# SCH_V1_3.net
KiCad netlist of a schematic drawn in Altium Designer
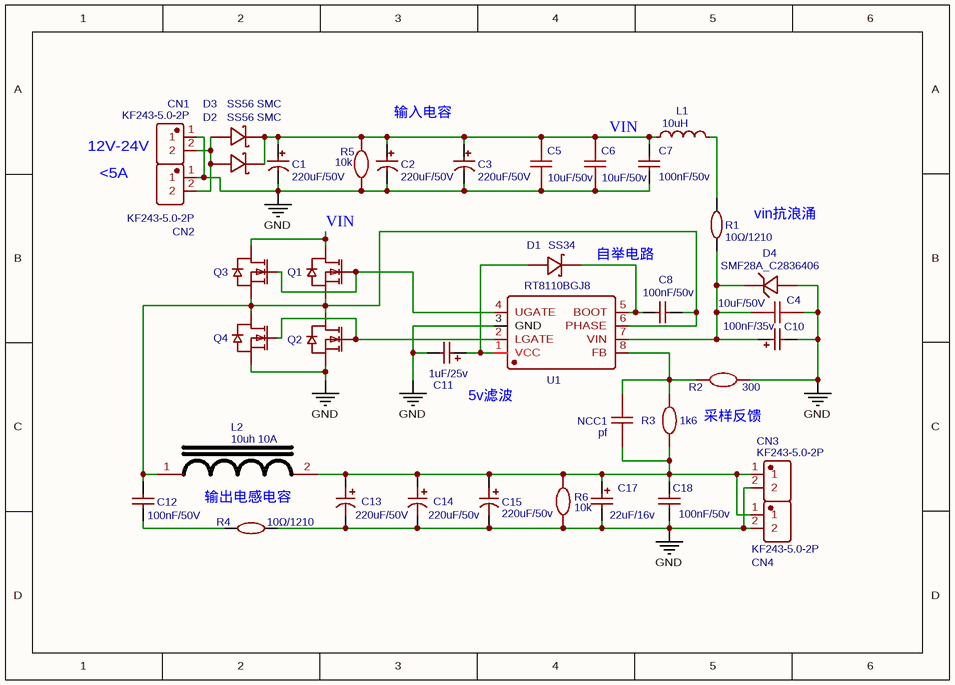
[diagram p0: SCH_V1.3.schdoc]

(export (version "E")
  (design (tool "Eeschema 10.0.6"))
  (components
    (comp (ref "C1")
      (value "220uF/50V")
      (footprint "CAP-TH_BD10.0-P5.00-D1.0-FD")
      (fields
        (field (name "BOM_SUPPLIER PART") "C338228")
        (field (name "BOM_MANUFACTURER PART") "50YXA220MEFC10X12.5")
        (field (name "CONTRIBUTOR") "LCSC")
      )
      (libsource (lib "altium-import") (part "root_3_220uF/50V_"))
    )
    (comp (ref "C2")
      (value "220uF/50V")
      (footprint "CAP-TH_BD10.0-P5.00-D1.0-FD")
      (fields
        (field (name "BOM_SUPPLIER PART") "C338228")
        (field (name "BOM_MANUFACTURER PART") "50YXA220MEFC10X12.5")
        (field (name "CONTRIBUTOR") "LCSC")
      )
      (libsource (lib "altium-import") (part "root_3_220uF/50V_"))
    )
    (comp (ref "C3")
      (value "220uF/50V")
      (footprint "CAP-TH_BD10.0-P5.00-D1.0-FD")
      (fields
        (field (name "BOM_SUPPLIER PART") "C338228")
        (field (name "BOM_MANUFACTURER PART") "50YXA220MEFC10X12.5")
        (field (name "CONTRIBUTOR") "LCSC")
      )
      (libsource (lib "altium-import") (part "root_3_220uF/50V_"))
    )
    (comp (ref "C4")
      (value "10uF/50V")
      (footprint "C1206")
      (fields
        (field (name "BOM_SUPPLIER PART") "C440198")
        (field (name "BOM_MANUFACTURER PART") "GRM21BR61H106KE43L")
        (field (name "CONTRIBUTOR") "LCSC")
      )
      (libsource (lib "altium-import") (part "root_0_10uF/50V_"))
    )
    (comp (ref "C5")
      (value "10uF/50v")
      (footprint "C1210")
      (fields
        (field (name "BOM_SUPPLIER PART") "C138687")
        (field (name "BOM_MANUFACTURER PART") "CL32B106KBJNNNE")
        (field (name "CONTRIBUTOR") "LCSC")
      )
      (libsource (lib "altium-import") (part "root_0_10uF/50v_"))
    )
    (comp (ref "C6")
      (value "10uF/50v")
      (footprint "C1210")
      (fields
        (field (name "BOM_SUPPLIER PART") "C138687")
        (field (name "BOM_MANUFACTURER PART") "CL32B106KBJNNNE")
        (field (name "CONTRIBUTOR") "LCSC")
      )
      (libsource (lib "altium-import") (part "root_0_10uF/50v_"))
    )
    (comp (ref "C7")
      (value "100nF/50v")
      (footprint "C1210")
      (fields
        (field (name "BOM_MANUFACTURER PART") "1210B104K500NT")
        (field (name "BOM_SUPPLIER PART") "C76567")
      )
      (libsource (lib "altium-import") (part "root_1_100nF/50v_"))
    )
    (comp (ref "C8")
      (value "100nF/50v")
      (footprint "C1210")
      (fields
        (field (name "BOM_MANUFACTURER PART") "1210B104K500NT")
        (field (name "BOM_SUPPLIER PART") "C76567")
      )
      (libsource (lib "altium-import") (part "root_2_100nF/50v_"))
    )
    (comp (ref "C10")
      (value "100nF/35v")
      (footprint "CAP-SMD_L3.2-W1.6")
      (fields
        (field (name "BOM_MANUFACTURER PART") "TAJA104K035RNJ")
        (field (name "BOM_SUPPLIER PART") "C7173")
      )
      (libsource (lib "altium-import") (part "root_2_100nF/35v_"))
    )
    (comp (ref "C11")
      (value "1uF/25v")
      (footprint "CAP-SMD_L3.2-W1.6-RD")
      (fields
        (field (name "BOM_MANUFACTURER PART") "TAJA105K025RNJ")
        (field (name "BOM_SUPPLIER PART") "C7175")
      )
      (libsource (lib "altium-import") (part "root_2_1uF/25v_"))
    )
    (comp (ref "C12")
      (value "100nF/50V")
      (footprint "C1210")
      (fields
        (field (name "BOM_MANUFACTURER PART") "1210B104K500NT")
        (field (name "BOM_SUPPLIER PART") "C76567")
      )
      (libsource (lib "altium-import") (part "root_1_100nF/50V_"))
    )
    (comp (ref "C13")
      (value "220uF/50V")
      (footprint "CAP-TH_BD10.0-P5.00-D0.6-FD")
      (fields
        (field (name "BOM_SUPPLIER PART") "C915761")
        (field (name "BOM_MANUFACTURER PART") "8221LFM1013H2RR00O")
        (field (name "CONTRIBUTOR") "LCSC")
      )
      (libsource (lib "") (part "root_3_220uF/50V__1"))
    )
    (comp (ref "C14")
      (value "220uF/50v")
      (footprint "CAP-TH_BD10.0-P5.00-D0.6-FD")
      (fields
        (field (name "BOM_SUPPLIER PART") "C915761")
        (field (name "BOM_MANUFACTURER PART") "8221LFM1013H2RR00O")
        (field (name "CONTRIBUTOR") "LCSC")
      )
      (libsource (lib "altium-import") (part "root_3_220uF/50v_"))
    )
    (comp (ref "C15")
      (value "220uF/50v")
      (footprint "CAP-TH_BD10.0-P5.00-D0.6-FD")
      (fields
        (field (name "BOM_SUPPLIER PART") "C915761")
        (field (name "BOM_MANUFACTURER PART") "8221LFM1013H2RR00O")
        (field (name "CONTRIBUTOR") "LCSC")
      )
      (libsource (lib "altium-import") (part "root_3_220uF/50v_"))
    )
    (comp (ref "C17")
      (value "22uF/16v")
      (footprint "CAP-SMD_L6.0-W3.2-R-RD")
      (fields
        (field (name "BOM_MANUFACTURER PART") "TAJC226K016RNJ")
        (field (name "BOM_SUPPLIER PART") "C11376")
      )
      (libsource (lib "altium-import") (part "root_1_22uF/16v_"))
    )
    (comp (ref "C18")
      (value "100nF/50v")
      (footprint "C1210")
      (fields
        (field (name "BOM_MANUFACTURER PART") "1210B104K500NT")
        (field (name "BOM_SUPPLIER PART") "C76567")
      )
      (libsource (lib "altium-import") (part "root_1_100nF/50v_"))
    )
    (comp (ref "CN1")
      (value "KF243-5.0-2P")
      (footprint "CONN-TH_P5.00_KF243-5.0-2P")
      (fields (field (name "BOM_SUPPLIER PART") "C475222") (field (name "CONTRIBUTOR") "LCSC"))
      (libsource (lib "altium-import") (part "root_0_KF243-5.0-2P_"))
    )
    (comp (ref "CN2")
      (value "KF243-5.0-2P")
      (footprint "CONN-TH_P5.00_KF243-5.0-2P")
      (fields (field (name "BOM_SUPPLIER PART") "C475222") (field (name "CONTRIBUTOR") "LCSC"))
      (libsource (lib "altium-import") (part "root_0_KF243-5.0-2P_"))
    )
    (comp (ref "CN3")
      (value "KF243-5.0-2P")
      (footprint "CONN-TH_P5.00_KF243-5.0-2P")
      (fields (field (name "BOM_SUPPLIER PART") "C475222") (field (name "CONTRIBUTOR") "LCSC"))
      (libsource (lib "") (part "root_0_KF243-5.0-2P__1"))
    )
    (comp (ref "CN4")
      (value "KF243-5.0-2P")
      (footprint "CONN-TH_P5.00_KF243-5.0-2P")
      (fields (field (name "BOM_SUPPLIER PART") "C475222") (field (name "CONTRIBUTOR") "LCSC"))
      (libsource (lib "") (part "root_0_KF243-5.0-2P__1"))
    )
    (comp (ref "D1")
      (value "SS34")
      (footprint "DO-214AC_L4.3-W2.7-LS5.3-RD")
      (fields (field (name "BOM_SUPPLIER PART") "C8678"))
      (libsource (lib "altium-import") (part "root_0_SS34_"))
    )
    (comp (ref "D2")
      (value "SS56 SMC")
      (footprint "SMC_L7.1-W6.2-LS8.1-R-RD")
      (fields (field (name "BOM_SUPPLIER PART") "C24138"))
      (libsource (lib "altium-import") (part "root_2_SS56 SMC_"))
    )
    (comp (ref "D3")
      (value "SS56 SMC")
      (footprint "SMC_L7.1-W6.2-LS8.1-R-RD")
      (fields (field (name "BOM_SUPPLIER PART") "C24138"))
      (libsource (lib "altium-import") (part "root_2_SS56 SMC_"))
    )
    (comp (ref "D4")
      (value "SMF28A_C2836406")
      (footprint "SOD-123FL_L2.8-W1.8-LS3.8-RD")
      (fields
        (field (name "BOM_SUPPLIER PART") "C2836406")
        (field (name "BOM_MANUFACTURER PART") "SMF28A")
        (field (name "CONTRIBUTOR") "LCSC")
      )
      (libsource (lib "altium-import") (part "root_0_SMF28A_C2836406_"))
    )
    (comp (ref "L1")
      (value "10uH")
      (footprint "L0805")
      (fields
        (field (name "BOM_SUPPLIER PART") "C281113")
        (field (name "BOM_MANUFACTURER PART") "MGFL2012F100MT-LF")
        (field (name "CONTRIBUTOR") "LCSC")
      )
      (libsource (lib "altium-import") (part "root_0_10uH_"))
    )
    (comp (ref "L2")
      (value "10uh 10A")
      (footprint "同步整流:L_R27cm_H11cm")
      (fields (field (name "CONTRIBUTOR") "Guest"))
      (libsource (lib "altium-import") (part "root_0_10uh 10A_"))
    )
    (comp (ref "NCC1")
      (value "pf")
      (footprint "C0603")
      (fields (field (name "CONTRIBUTOR") "LCEDA_Lib"))
      (libsource (lib "altium-import") (part "root_1_pf_"))
    )
    (comp (ref "Q1")
      (value "AOD442G-MS")
      (footprint "TO-252-3_L6.6-W6.1-P4.57-LS9.9-BR-CW")
      (fields (field (name "BOM_SUPPLIER PART") "C2982213") (field (name "CONTRIBUTOR") "LCSC"))
      (libsource (lib "altium-import") (part "root_0_AOD442G-MS_"))
    )
    (comp (ref "Q2")
      (value "AOD442G-MS")
      (footprint "TO-252-3_L6.6-W6.1-P4.57-LS9.9-BR-CW")
      (fields (field (name "BOM_SUPPLIER PART") "C2982213") (field (name "CONTRIBUTOR") "LCSC"))
      (libsource (lib "altium-import") (part "root_0_AOD442G-MS_"))
    )
    (comp (ref "Q3")
      (value "AOD442G-MS")
      (footprint "TO-252-3_L6.6-W6.1-P4.57-LS9.9-BR-CW")
      (fields (field (name "BOM_SUPPLIER PART") "C2982213") (field (name "CONTRIBUTOR") "LCSC"))
      (libsource (lib "altium-import") (part "root_0_AOD442G-MS_"))
    )
    (comp (ref "Q4")
      (value "AOD442G-MS")
      (footprint "TO-252-3_L6.6-W6.1-P4.57-LS9.9-BR-CW")
      (fields (field (name "BOM_SUPPLIER PART") "C2982213") (field (name "CONTRIBUTOR") "LCSC"))
      (libsource (lib "altium-import") (part "root_0_AOD442G-MS_"))
    )
    (comp (ref "R1")
      (value "10Ω/1210")
      (footprint "R1210")
      (fields
        (field (name "BOM_MANUFACTURER PART") "1210W3F100JT5E")
        (field (name "BOM_SUPPLIER PART") "C44451")
      )
      (libsource (lib "altium-import") (part "root_1_10Ω/1210_"))
    )
    (comp (ref "R2")
      (value "300")
      (footprint "R0603")
      (fields (field (name "CONTRIBUTOR") "LCEDA_Lib"))
      (libsource (lib "altium-import") (part "root_0_300_"))
    )
    (comp (ref "R3")
      (value "1k6")
      (footprint "R0603")
      (fields (field (name "CONTRIBUTOR") "LCEDA_Lib"))
      (libsource (lib "altium-import") (part "root_1_1k6_"))
    )
    (comp (ref "R4")
      (value "10Ω/1210")
      (footprint "R1210")
      (fields
        (field (name "BOM_MANUFACTURER PART") "1210W3F100JT5E")
        (field (name "BOM_SUPPLIER PART") "C44451")
      )
      (libsource (lib "altium-import") (part "root_0_10Ω/1210_"))
    )
    (comp (ref "R5")
      (value "10k")
      (footprint "R0805")
      (fields (field (name "CONTRIBUTOR") "LCEDA_Lib"))
      (libsource (lib "altium-import") (part "root_1_300_"))
    )
    (comp (ref "R6")
      (value "10k")
      (footprint "R0805")
      (fields (field (name "CONTRIBUTOR") "LCEDA_Lib"))
      (libsource (lib "altium-import") (part "root_1_300_"))
    )
    (comp (ref "U1")
      (value "RT8110BGJ8")
      (footprint "TSOT-23-8_L2.9-W1.6-P0.65-LS2.8-BR")
      (fields (field (name "BOM_SUPPLIER PART") "C27917"))
      (libsource (lib "altium-import") (part "root_0_RT8110BGJ8_"))
    )
  )
  (nets
    (net (code "1") (name "/VIN") (class "Default")
      (node (ref "C1") (pin "1") (pinfunction "1_1") (pintype "passive"))
      (node (ref "C2") (pin "1") (pinfunction "1_1") (pintype "passive"))
      (node (ref "C3") (pin "1") (pinfunction "1_1") (pintype "passive"))
      (node (ref "C5") (pin "2") (pinfunction "2_2") (pintype "passive"))
      (node (ref "C6") (pin "2") (pinfunction "2_2") (pintype "passive"))
      (node (ref "C7") (pin "2") (pinfunction "2_2") (pintype "passive"))
      (node (ref "D2") (pin "2") (pinfunction "K_2") (pintype "passive"))
      (node (ref "D3") (pin "2") (pinfunction "K_2") (pintype "passive"))
      (node (ref "L1") (pin "2") (pinfunction "2_2") (pintype "passive"))
      (node (ref "Q1") (pin "2") (pinfunction "D_2") (pintype "passive"))
      (node (ref "Q3") (pin "2") (pinfunction "D_2") (pintype "passive"))
      (node (ref "R5") (pin "2") (pinfunction "2_2") (pintype "passive"))
    )
    (net (code "2") (name "GND") (class "Default")
      (node (ref "C1") (pin "2") (pinfunction "2_2") (pintype "passive"))
      (node (ref "C10") (pin "2") (pinfunction "2_2") (pintype "passive"))
      (node (ref "C11") (pin "2") (pinfunction "2_2") (pintype "passive"))
      (node (ref "C13") (pin "2") (pinfunction "2_2") (pintype "passive"))
      (node (ref "C14") (pin "2") (pinfunction "2_2") (pintype "passive"))
      (node (ref "C15") (pin "2") (pinfunction "2_2") (pintype "passive"))
      (node (ref "C17") (pin "2") (pinfunction "2_2") (pintype "passive"))
      (node (ref "C18") (pin "1") (pinfunction "1_1") (pintype "passive"))
      (node (ref "C2") (pin "2") (pinfunction "2_2") (pintype "passive"))
      (node (ref "C3") (pin "2") (pinfunction "2_2") (pintype "passive"))
      (node (ref "C4") (pin "2") (pinfunction "2_2") (pintype "passive"))
      (node (ref "C5") (pin "1") (pinfunction "1_1") (pintype "passive"))
      (node (ref "C6") (pin "1") (pinfunction "1_1") (pintype "passive"))
      (node (ref "C7") (pin "1") (pinfunction "1_1") (pintype "passive"))
      (node (ref "CN1") (pin "1") (pinfunction "1_1") (pintype "passive"))
      (node (ref "CN2") (pin "1") (pinfunction "1_1") (pintype "passive"))
      (node (ref "CN3") (pin "2") (pinfunction "2_2") (pintype "passive"))
      (node (ref "CN4") (pin "2") (pinfunction "2_2") (pintype "passive"))
      (node (ref "D4") (pin "2") (pinfunction "A_2") (pintype "passive"))
      (node (ref "Q2") (pin "3") (pinfunction "S_3") (pintype "passive"))
      (node (ref "Q4") (pin "3") (pinfunction "S_3") (pintype "passive"))
      (node (ref "R2") (pin "2") (pinfunction "2_2") (pintype "passive"))
      (node (ref "R4") (pin "2") (pinfunction "2_2") (pintype "passive"))
      (node (ref "R5") (pin "1") (pinfunction "1_1") (pintype "passive"))
      (node (ref "R6") (pin "1") (pinfunction "1_1") (pintype "passive"))
      (node (ref "U1") (pin "3") (pinfunction "GND_3") (pintype "passive"))
    )
    (net (code "3") (name "Net-(C12-Pad1)") (class "Default")
      (node (ref "C12") (pin "1") (pinfunction "1_1") (pintype "passive"))
      (node (ref "R4") (pin "1") (pinfunction "1_1") (pintype "passive"))
    )
    (net (code "4") (name "Net-(C13-Pad1)") (class "Default")
      (node (ref "C13") (pin "1") (pinfunction "1_1") (pintype "passive"))
      (node (ref "C14") (pin "1") (pinfunction "1_1") (pintype "passive"))
      (node (ref "C15") (pin "1") (pinfunction "1_1") (pintype "passive"))
      (node (ref "C17") (pin "1") (pinfunction "1_1") (pintype "passive"))
      (node (ref "C18") (pin "2") (pinfunction "2_2") (pintype "passive"))
      (node (ref "CN3") (pin "1") (pinfunction "1_1") (pintype "passive"))
      (node (ref "CN4") (pin "1") (pinfunction "1_1") (pintype "passive"))
      (node (ref "L2") (pin "2") (pinfunction "2_2") (pintype "passive"))
      (node (ref "NCC1") (pin "1") (pinfunction "1_1") (pintype "passive"))
      (node (ref "R3") (pin "1") (pinfunction "1_1") (pintype "passive"))
      (node (ref "R6") (pin "2") (pinfunction "2_2") (pintype "passive"))
    )
    (net (code "5") (name "Net-(D1-A)") (class "Default")
      (node (ref "C11") (pin "1") (pinfunction "1_1") (pintype "passive"))
      (node (ref "D1") (pin "2") (pinfunction "A_2") (pintype "passive"))
      (node (ref "U1") (pin "1") (pinfunction "VCC_1") (pintype "passive"))
    )
    (net (code "6") (name "Net-(D1-K)") (class "Default")
      (node (ref "C8") (pin "1") (pinfunction "1_1") (pintype "passive"))
      (node (ref "D1") (pin "1") (pinfunction "K_1") (pintype "passive"))
      (node (ref "U1") (pin "5") (pinfunction "BOOT_5") (pintype "passive"))
    )
    (net (code "7") (name "Net-(D2-A)") (class "Default")
      (node (ref "CN1") (pin "2") (pinfunction "2_2") (pintype "passive"))
      (node (ref "CN2") (pin "2") (pinfunction "2_2") (pintype "passive"))
      (node (ref "D2") (pin "1") (pinfunction "A_1") (pintype "passive"))
      (node (ref "D3") (pin "1") (pinfunction "A_1") (pintype "passive"))
    )
    (net (code "8") (name "Net-(D4-C)") (class "Default")
      (node (ref "C10") (pin "1") (pinfunction "1_1") (pintype "passive"))
      (node (ref "C4") (pin "1") (pinfunction "1_1") (pintype "passive"))
      (node (ref "D4") (pin "1") (pinfunction "C_1") (pintype "passive"))
      (node (ref "R1") (pin "1") (pinfunction "1_1") (pintype "passive"))
      (node (ref "U1") (pin "7") (pinfunction "VIN_7") (pintype "passive"))
    )
    (net (code "9") (name "Net-(L1-Pad1)") (class "Default")
      (node (ref "L1") (pin "1") (pinfunction "1_1") (pintype "passive"))
      (node (ref "R1") (pin "2") (pinfunction "2_2") (pintype "passive"))
    )
    (net (code "10") (name "Net-(Q1-G)") (class "Default")
      (node (ref "Q1") (pin "1") (pinfunction "G_1") (pintype "passive"))
      (node (ref "Q3") (pin "1") (pinfunction "G_1") (pintype "passive"))
      (node (ref "U1") (pin "4") (pinfunction "UGATE_4") (pintype "passive"))
    )
    (net (code "11") (name "Net-(Q1-S)") (class "Default")
      (node (ref "C12") (pin "2") (pinfunction "2_2") (pintype "passive"))
      (node (ref "C8") (pin "2") (pinfunction "2_2") (pintype "passive"))
      (node (ref "L2") (pin "1") (pinfunction "1_1") (pintype "passive"))
      (node (ref "Q1") (pin "3") (pinfunction "S_3") (pintype "passive"))
      (node (ref "Q2") (pin "2") (pinfunction "D_2") (pintype "passive"))
      (node (ref "Q3") (pin "3") (pinfunction "S_3") (pintype "passive"))
      (node (ref "Q4") (pin "2") (pinfunction "D_2") (pintype "passive"))
      (node (ref "U1") (pin "6") (pinfunction "PHASE_6") (pintype "passive"))
    )
    (net (code "12") (name "Net-(Q2-G)") (class "Default")
      (node (ref "Q2") (pin "1") (pinfunction "G_1") (pintype "passive"))
      (node (ref "Q4") (pin "1") (pinfunction "G_1") (pintype "passive"))
      (node (ref "U1") (pin "2") (pinfunction "LGATE_2") (pintype "passive"))
    )
    (net (code "13") (name "Net-(U1-FB)") (class "Default")
      (node (ref "NCC1") (pin "2") (pinfunction "2_2") (pintype "passive"))
      (node (ref "R2") (pin "1") (pinfunction "1_1") (pintype "passive"))
      (node (ref "R3") (pin "2") (pinfunction "2_2") (pintype "passive"))
      (node (ref "U1") (pin "8") (pinfunction "FB_8") (pintype "passive"))
    )
  )
)
